# Hardware-Neuron.net
KiCad netlist of a schematic drawn in EAGLE
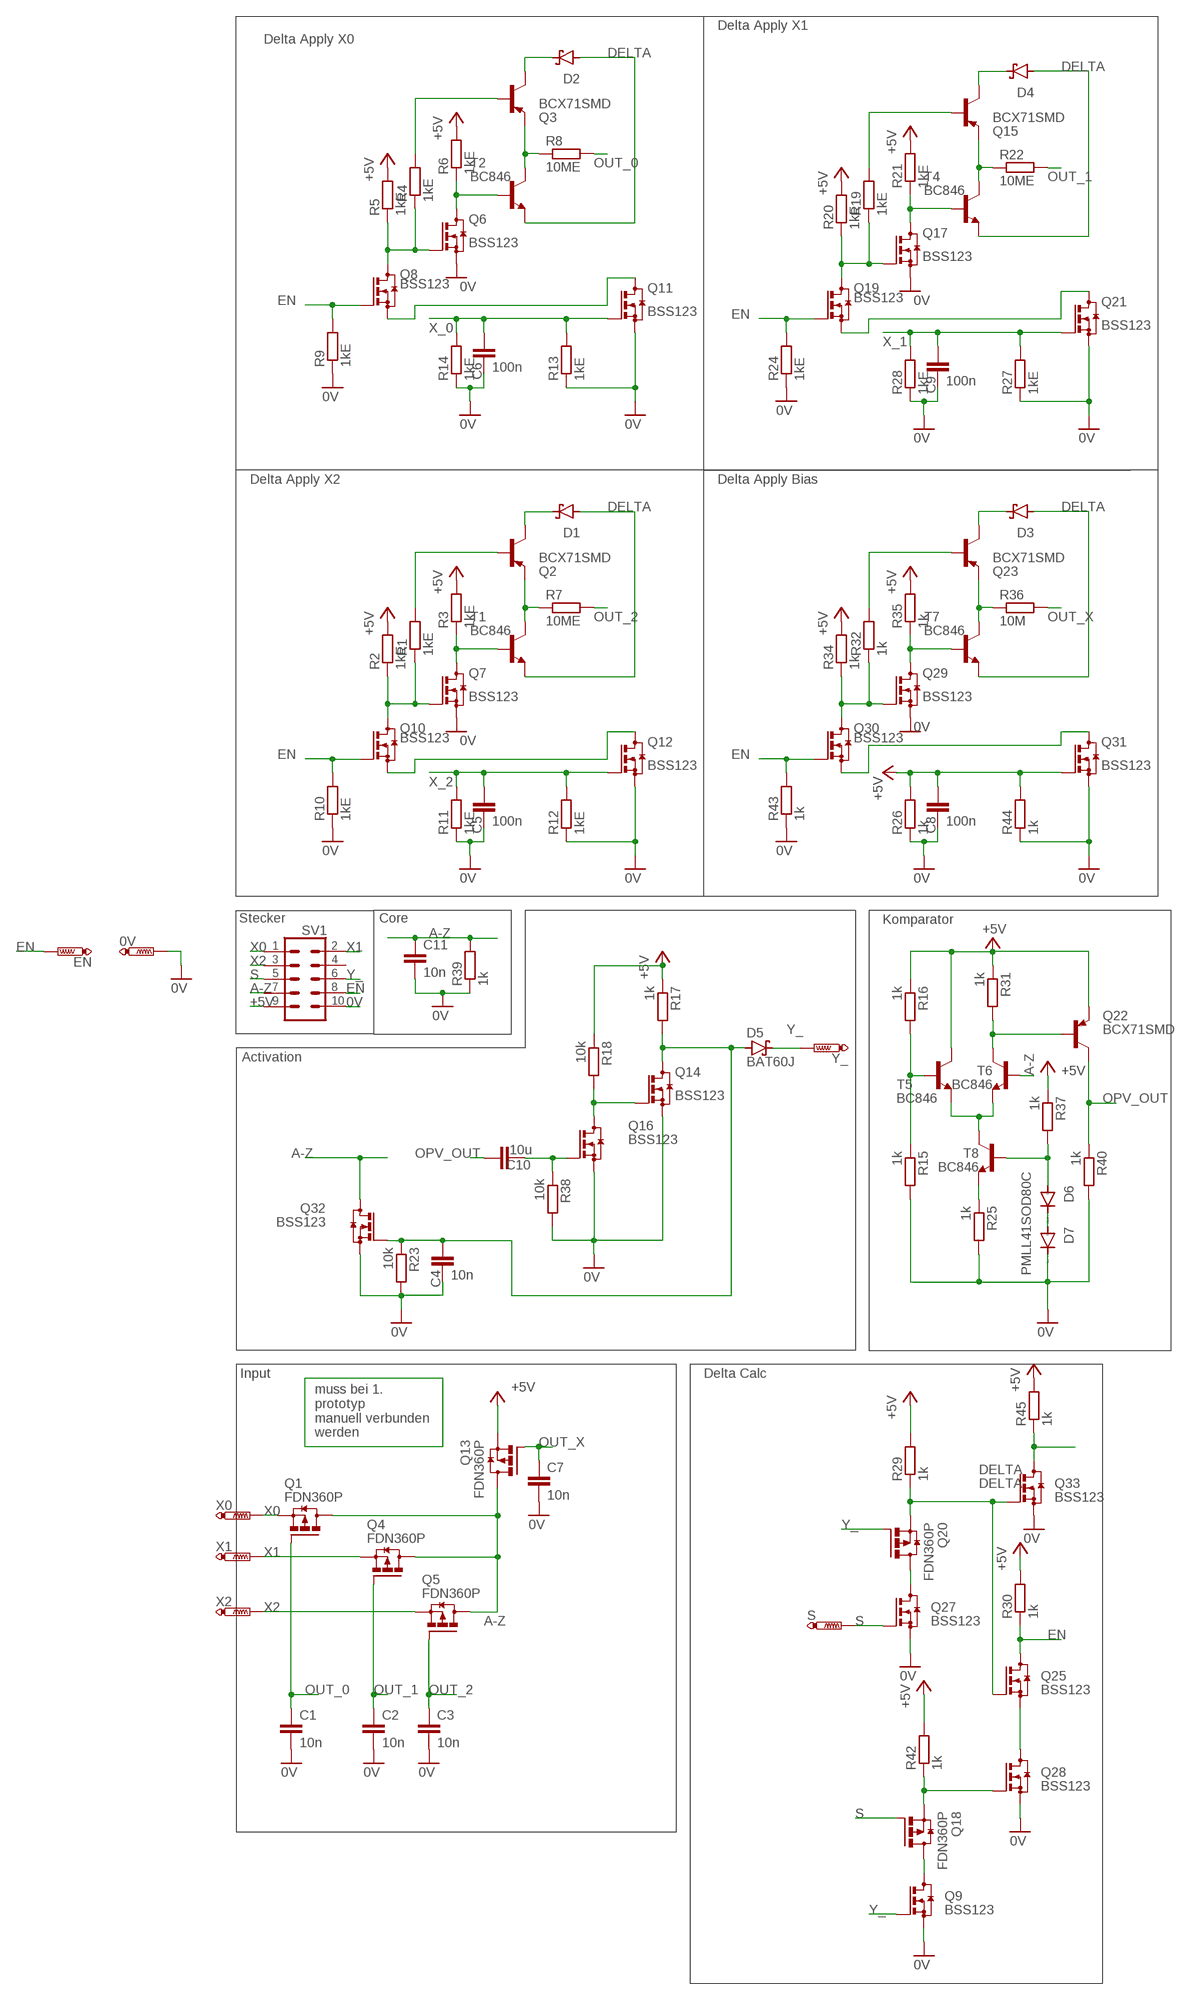
[diagram p0: schematic, sheet 1]

(export (version "E")
  (design (tool "Eeschema 10.0.6"))
  (components
    (comp (ref "0V")
      (value "PTR1PAD1-17")
      (footprint "eagle-import:P1-17")
      (libsource (lib "eagle-import") (part "PTR1PAD1-17"))
    )
    (comp (ref "C1")
      (value "10n")
      (footprint "eagle-import:C0805")
      (libsource (lib "eagle-import") (part "C-EUC0805"))
    )
    (comp (ref "C2")
      (value "10n")
      (footprint "eagle-import:C0805")
      (libsource (lib "eagle-import") (part "C-EUC0805"))
    )
    (comp (ref "C3")
      (value "10n")
      (footprint "eagle-import:C0805")
      (libsource (lib "eagle-import") (part "C-EUC0805"))
    )
    (comp (ref "C4")
      (value "10n")
      (footprint "eagle-import:C0805")
      (libsource (lib "eagle-import") (part "C-EUC0805"))
    )
    (comp (ref "C5")
      (value "100n")
      (footprint "eagle-import:C0805")
      (libsource (lib "eagle-import") (part "C-EUC0805"))
    )
    (comp (ref "C6")
      (value "100n")
      (footprint "eagle-import:C0805")
      (libsource (lib "eagle-import") (part "C-EUC0805"))
    )
    (comp (ref "C7")
      (value "10n")
      (footprint "eagle-import:C0805")
      (libsource (lib "eagle-import") (part "C-EUC0805"))
    )
    (comp (ref "C8")
      (value "100n")
      (footprint "eagle-import:C0805")
      (libsource (lib "eagle-import") (part "C-EUC0805"))
    )
    (comp (ref "C9")
      (value "100n")
      (footprint "eagle-import:C0805")
      (libsource (lib "eagle-import") (part "C-EUC0805"))
    )
    (comp (ref "C10")
      (value "10u")
      (footprint "eagle-import:C0805")
      (libsource (lib "eagle-import") (part "C-EUC0805"))
    )
    (comp (ref "C11")
      (value "10n")
      (footprint "eagle-import:C0805")
      (libsource (lib "eagle-import") (part "C-EUC0805"))
    )
    (comp (ref "D1")
      (value "BAT60J")
      (footprint "eagle-import:SOD323_ST")
      (libsource (lib "eagle-import") (part "BAT60J"))
    )
    (comp (ref "D2")
      (value "BAT60J")
      (footprint "eagle-import:SOD323_ST")
      (libsource (lib "eagle-import") (part "BAT60J"))
    )
    (comp (ref "D3")
      (value "BAT60J")
      (footprint "eagle-import:SOD323_ST")
      (libsource (lib "eagle-import") (part "BAT60J"))
    )
    (comp (ref "D4")
      (value "BAT60J")
      (footprint "eagle-import:SOD323_ST")
      (libsource (lib "eagle-import") (part "BAT60J"))
    )
    (comp (ref "D5")
      (value "BAT60J")
      (footprint "eagle-import:SOD323_ST")
      (libsource (lib "eagle-import") (part "BAT60J"))
    )
    (comp (ref "D6")
      (value "PMLL41SOD80C")
      (footprint "eagle-import:SOD80C")
      (libsource (lib "eagle-import") (part "PMLL41SOD80C"))
    )
    (comp (ref "D7")
      (value "PMLL41SOD80C")
      (footprint "eagle-import:SOD80C")
      (libsource (lib "eagle-import") (part "PMLL41SOD80C"))
    )
    (comp (ref "EN")
      (value "PTR1PAD1-17")
      (footprint "eagle-import:P1-17")
      (libsource (lib "eagle-import") (part "PTR1PAD1-17"))
    )
    (comp (ref "Q1")
      (value "FDN360P")
      (footprint "eagle-import:SUPER-SOT3")
      (libsource (lib "eagle-import") (part "FDN360P"))
    )
    (comp (ref "Q2")
      (value "BCX71SMD")
      (footprint "eagle-import:SOT23")
      (libsource (lib "eagle-import") (part "BCX71SMD"))
    )
    (comp (ref "Q3")
      (value "BCX71SMD")
      (footprint "eagle-import:SOT23")
      (libsource (lib "eagle-import") (part "BCX71SMD"))
    )
    (comp (ref "Q4")
      (value "FDN360P")
      (footprint "eagle-import:SUPER-SOT3")
      (libsource (lib "eagle-import") (part "FDN360P"))
    )
    (comp (ref "Q5")
      (value "FDN360P")
      (footprint "eagle-import:SUPER-SOT3")
      (libsource (lib "eagle-import") (part "FDN360P"))
    )
    (comp (ref "Q6")
      (value "BSS123")
      (footprint "eagle-import:SOT23")
      (libsource (lib "eagle-import") (part "BSS123"))
    )
    (comp (ref "Q7")
      (value "BSS123")
      (footprint "eagle-import:SOT23")
      (libsource (lib "eagle-import") (part "BSS123"))
    )
    (comp (ref "Q8")
      (value "BSS123")
      (footprint "eagle-import:SOT23")
      (libsource (lib "eagle-import") (part "BSS123"))
    )
    (comp (ref "Q9")
      (value "BSS123")
      (footprint "eagle-import:SOT23")
      (libsource (lib "eagle-import") (part "BSS123"))
    )
    (comp (ref "Q10")
      (value "BSS123")
      (footprint "eagle-import:SOT23")
      (libsource (lib "eagle-import") (part "BSS123"))
    )
    (comp (ref "Q11")
      (value "BSS123")
      (footprint "eagle-import:SOT23")
      (libsource (lib "eagle-import") (part "BSS123"))
    )
    (comp (ref "Q12")
      (value "BSS123")
      (footprint "eagle-import:SOT23")
      (libsource (lib "eagle-import") (part "BSS123"))
    )
    (comp (ref "Q13")
      (value "FDN360P")
      (footprint "eagle-import:SUPER-SOT3")
      (libsource (lib "eagle-import") (part "FDN360P"))
    )
    (comp (ref "Q14")
      (value "BSS123")
      (footprint "eagle-import:SOT23")
      (libsource (lib "eagle-import") (part "BSS123"))
    )
    (comp (ref "Q15")
      (value "BCX71SMD")
      (footprint "eagle-import:SOT23")
      (libsource (lib "eagle-import") (part "BCX71SMD"))
    )
    (comp (ref "Q16")
      (value "BSS123")
      (footprint "eagle-import:SOT23")
      (libsource (lib "eagle-import") (part "BSS123"))
    )
    (comp (ref "Q17")
      (value "BSS123")
      (footprint "eagle-import:SOT23")
      (libsource (lib "eagle-import") (part "BSS123"))
    )
    (comp (ref "Q18")
      (value "FDN360P")
      (footprint "eagle-import:SUPER-SOT3")
      (libsource (lib "eagle-import") (part "FDN360P"))
    )
    (comp (ref "Q19")
      (value "BSS123")
      (footprint "eagle-import:SOT23")
      (libsource (lib "eagle-import") (part "BSS123"))
    )
    (comp (ref "Q20")
      (value "FDN360P")
      (footprint "eagle-import:SUPER-SOT3")
      (libsource (lib "eagle-import") (part "FDN360P"))
    )
    (comp (ref "Q21")
      (value "BSS123")
      (footprint "eagle-import:SOT23")
      (libsource (lib "eagle-import") (part "BSS123"))
    )
    (comp (ref "Q22")
      (value "BCX71SMD")
      (footprint "eagle-import:SOT23")
      (libsource (lib "eagle-import") (part "BCX71SMD"))
    )
    (comp (ref "Q23")
      (value "BCX71SMD")
      (footprint "eagle-import:SOT23")
      (libsource (lib "eagle-import") (part "BCX71SMD"))
    )
    (comp (ref "Q25")
      (value "BSS123")
      (footprint "eagle-import:SOT23")
      (libsource (lib "eagle-import") (part "BSS123"))
    )
    (comp (ref "Q27")
      (value "BSS123")
      (footprint "eagle-import:SOT23")
      (libsource (lib "eagle-import") (part "BSS123"))
    )
    (comp (ref "Q28")
      (value "BSS123")
      (footprint "eagle-import:SOT23")
      (libsource (lib "eagle-import") (part "BSS123"))
    )
    (comp (ref "Q29")
      (value "BSS123")
      (footprint "eagle-import:SOT23")
      (libsource (lib "eagle-import") (part "BSS123"))
    )
    (comp (ref "Q30")
      (value "BSS123")
      (footprint "eagle-import:SOT23")
      (libsource (lib "eagle-import") (part "BSS123"))
    )
    (comp (ref "Q31")
      (value "BSS123")
      (footprint "eagle-import:SOT23")
      (libsource (lib "eagle-import") (part "BSS123"))
    )
    (comp (ref "Q32")
      (value "BSS123")
      (footprint "eagle-import:SOT23")
      (libsource (lib "eagle-import") (part "BSS123"))
    )
    (comp (ref "Q33")
      (value "BSS123")
      (footprint "eagle-import:SOT23")
      (libsource (lib "eagle-import") (part "BSS123"))
    )
    (comp (ref "R1")
      (value "1kE")
      (footprint "eagle-import:M0805")
      (libsource (lib "eagle-import") (part "R-EU_M0805"))
    )
    (comp (ref "R2")
      (value "1kE")
      (footprint "eagle-import:M0805")
      (libsource (lib "eagle-import") (part "R-EU_M0805"))
    )
    (comp (ref "R3")
      (value "1kE")
      (footprint "eagle-import:M0805")
      (libsource (lib "eagle-import") (part "R-EU_M0805"))
    )
    (comp (ref "R4")
      (value "1kE")
      (footprint "eagle-import:M0805")
      (libsource (lib "eagle-import") (part "R-EU_M0805"))
    )
    (comp (ref "R5")
      (value "1kE")
      (footprint "eagle-import:M0805")
      (libsource (lib "eagle-import") (part "R-EU_M0805"))
    )
    (comp (ref "R6")
      (value "1kE")
      (footprint "eagle-import:M0805")
      (libsource (lib "eagle-import") (part "R-EU_M0805"))
    )
    (comp (ref "R7")
      (value "10ME")
      (footprint "eagle-import:M0805")
      (libsource (lib "eagle-import") (part "R-EU_M0805"))
    )
    (comp (ref "R8")
      (value "10ME")
      (footprint "eagle-import:M0805")
      (libsource (lib "eagle-import") (part "R-EU_M0805"))
    )
    (comp (ref "R9")
      (value "1kE")
      (footprint "eagle-import:M0805")
      (libsource (lib "eagle-import") (part "R-EU_M0805"))
    )
    (comp (ref "R10")
      (value "1kE")
      (footprint "eagle-import:M0805")
      (libsource (lib "eagle-import") (part "R-EU_M0805"))
    )
    (comp (ref "R11")
      (value "1kE")
      (footprint "eagle-import:M0805")
      (libsource (lib "eagle-import") (part "R-EU_M0805"))
    )
    (comp (ref "R12")
      (value "1kE")
      (footprint "eagle-import:M0805")
      (libsource (lib "eagle-import") (part "R-EU_M0805"))
    )
    (comp (ref "R13")
      (value "1kE")
      (footprint "eagle-import:M0805")
      (libsource (lib "eagle-import") (part "R-EU_M0805"))
    )
    (comp (ref "R14")
      (value "1kE")
      (footprint "eagle-import:M0805")
      (libsource (lib "eagle-import") (part "R-EU_M0805"))
    )
    (comp (ref "R15")
      (value "1k")
      (footprint "eagle-import:M0805")
      (libsource (lib "eagle-import") (part "R-EU_M0805"))
    )
    (comp (ref "R16")
      (value "1k")
      (footprint "eagle-import:M0805")
      (libsource (lib "eagle-import") (part "R-EU_M0805"))
    )
    (comp (ref "R17")
      (value "1k")
      (footprint "eagle-import:M0805")
      (libsource (lib "eagle-import") (part "R-EU_M0805"))
    )
    (comp (ref "R18")
      (value "10k")
      (footprint "eagle-import:M0805")
      (libsource (lib "eagle-import") (part "R-EU_M0805"))
    )
    (comp (ref "R19")
      (value "1kE")
      (footprint "eagle-import:M0805")
      (libsource (lib "eagle-import") (part "R-EU_M0805"))
    )
    (comp (ref "R20")
      (value "1kE")
      (footprint "eagle-import:M0805")
      (libsource (lib "eagle-import") (part "R-EU_M0805"))
    )
    (comp (ref "R21")
      (value "1kE")
      (footprint "eagle-import:M0805")
      (libsource (lib "eagle-import") (part "R-EU_M0805"))
    )
    (comp (ref "R22")
      (value "10ME")
      (footprint "eagle-import:M0805")
      (libsource (lib "eagle-import") (part "R-EU_M0805"))
    )
    (comp (ref "R23")
      (value "10k")
      (footprint "eagle-import:M0805")
      (libsource (lib "eagle-import") (part "R-EU_M0805"))
    )
    (comp (ref "R24")
      (value "1kE")
      (footprint "eagle-import:M0805")
      (libsource (lib "eagle-import") (part "R-EU_M0805"))
    )
    (comp (ref "R25")
      (value "1k")
      (footprint "eagle-import:M0805")
      (libsource (lib "eagle-import") (part "R-EU_M0805"))
    )
    (comp (ref "R26")
      (value "1k")
      (footprint "eagle-import:M0805")
      (libsource (lib "eagle-import") (part "R-EU_M0805"))
    )
    (comp (ref "R27")
      (value "1kE")
      (footprint "eagle-import:M0805")
      (libsource (lib "eagle-import") (part "R-EU_M0805"))
    )
    (comp (ref "R28")
      (value "1kE")
      (footprint "eagle-import:M0805")
      (libsource (lib "eagle-import") (part "R-EU_M0805"))
    )
    (comp (ref "R29")
      (value "1k")
      (footprint "eagle-import:M0805")
      (libsource (lib "eagle-import") (part "R-EU_M0805"))
    )
    (comp (ref "R30")
      (value "1k")
      (footprint "eagle-import:M0805")
      (libsource (lib "eagle-import") (part "R-EU_M0805"))
    )
    (comp (ref "R31")
      (value "1k")
      (footprint "eagle-import:M0805")
      (libsource (lib "eagle-import") (part "R-EU_M0805"))
    )
    (comp (ref "R32")
      (value "1k")
      (footprint "eagle-import:M0805")
      (libsource (lib "eagle-import") (part "R-EU_M0805"))
    )
    (comp (ref "R34")
      (value "1k")
      (footprint "eagle-import:M0805")
      (libsource (lib "eagle-import") (part "R-EU_M0805"))
    )
    (comp (ref "R35")
      (value "1k")
      (footprint "eagle-import:M0805")
      (libsource (lib "eagle-import") (part "R-EU_M0805"))
    )
    (comp (ref "R36")
      (value "10M")
      (footprint "eagle-import:M0805")
      (libsource (lib "eagle-import") (part "R-EU_M0805"))
    )
    (comp (ref "R37")
      (value "1k")
      (footprint "eagle-import:M0805")
      (libsource (lib "eagle-import") (part "R-EU_M0805"))
    )
    (comp (ref "R38")
      (value "10k")
      (footprint "eagle-import:M0805")
      (libsource (lib "eagle-import") (part "R-EU_M0805"))
    )
    (comp (ref "R39")
      (value "1k")
      (footprint "eagle-import:M0805")
      (libsource (lib "eagle-import") (part "R-EU_M0805"))
    )
    (comp (ref "R40")
      (value "1k")
      (footprint "eagle-import:M0805")
      (libsource (lib "eagle-import") (part "R-EU_M0805"))
    )
    (comp (ref "R42")
      (value "1k")
      (footprint "eagle-import:M0805")
      (libsource (lib "eagle-import") (part "R-EU_M0805"))
    )
    (comp (ref "R43")
      (value "1k")
      (footprint "eagle-import:M0805")
      (libsource (lib "eagle-import") (part "R-EU_M0805"))
    )
    (comp (ref "R44")
      (value "1k")
      (footprint "eagle-import:M0805")
      (libsource (lib "eagle-import") (part "R-EU_M0805"))
    )
    (comp (ref "R45")
      (value "1k")
      (footprint "eagle-import:M0805")
      (libsource (lib "eagle-import") (part "R-EU_M0805"))
    )
    (comp (ref "S")
      (value "PTR1PAD1-17")
      (footprint "eagle-import:P1-17")
      (libsource (lib "eagle-import") (part "PTR1PAD1-17"))
    )
    (comp (ref "SV1")
      (value "ML10")
      (footprint "eagle-import:ML10")
      (libsource (lib "eagle-import") (part "ML10"))
    )
    (comp (ref "T1")
      (value "BC846")
      (footprint "eagle-import:SOT23")
      (libsource (lib "eagle-import") (part "BC846"))
    )
    (comp (ref "T2")
      (value "BC846")
      (footprint "eagle-import:SOT23")
      (libsource (lib "eagle-import") (part "BC846"))
    )
    (comp (ref "T4")
      (value "BC846")
      (footprint "eagle-import:SOT23")
      (libsource (lib "eagle-import") (part "BC846"))
    )
    (comp (ref "T5")
      (value "BC846")
      (footprint "eagle-import:SOT23")
      (libsource (lib "eagle-import") (part "BC846"))
    )
    (comp (ref "T6")
      (value "BC846")
      (footprint "eagle-import:SOT23")
      (libsource (lib "eagle-import") (part "BC846"))
    )
    (comp (ref "T7")
      (value "BC846")
      (footprint "eagle-import:SOT23")
      (libsource (lib "eagle-import") (part "BC846"))
    )
    (comp (ref "T8")
      (value "BC846")
      (footprint "eagle-import:SOT23")
      (libsource (lib "eagle-import") (part "BC846"))
    )
    (comp (ref "X0")
      (value "PTR1PAD1-17")
      (footprint "eagle-import:P1-17")
      (libsource (lib "eagle-import") (part "PTR1PAD1-17"))
    )
    (comp (ref "X1")
      (value "PTR1PAD1-17")
      (footprint "eagle-import:P1-17")
      (libsource (lib "eagle-import") (part "PTR1PAD1-17"))
    )
    (comp (ref "X2")
      (value "PTR1PAD1-17")
      (footprint "eagle-import:P1-17")
      (libsource (lib "eagle-import") (part "PTR1PAD1-17"))
    )
    (comp (ref "Y_")
      (value "PTR1PAD1-17")
      (footprint "eagle-import:P1-17")
      (libsource (lib "eagle-import") (part "PTR1PAD1-17"))
    )
  )
  (nets
    (net (code "1") (name "+5V") (class "Default")
      (node (ref "C8") (pin "1") (pinfunction "1_1") (pintype "passive"))
      (node (ref "Q13") (pin "2") (pinfunction "S_2") (pintype "passive"))
      (node (ref "Q22") (pin "2") (pinfunction "E_2") (pintype "passive"))
      (node (ref "Q31") (pin "1") (pinfunction "G_1") (pintype "passive"))
      (node (ref "R16") (pin "1") (pinfunction "1_1") (pintype "passive"))
      (node (ref "R17") (pin "1") (pinfunction "1_1") (pintype "passive"))
      (node (ref "R18") (pin "1") (pinfunction "1_1") (pintype "passive"))
      (node (ref "R2") (pin "2") (pinfunction "2_2") (pintype "passive"))
      (node (ref "R20") (pin "2") (pinfunction "2_2") (pintype "passive"))
      (node (ref "R21") (pin "2") (pinfunction "2_2") (pintype "passive"))
      (node (ref "R26") (pin "2") (pinfunction "2_2") (pintype "passive"))
      (node (ref "R29") (pin "2") (pinfunction "2_2") (pintype "passive"))
      (node (ref "R3") (pin "2") (pinfunction "2_2") (pintype "passive"))
      (node (ref "R30") (pin "2") (pinfunction "2_2") (pintype "passive"))
      (node (ref "R31") (pin "1") (pinfunction "1_1") (pintype "passive"))
      (node (ref "R34") (pin "2") (pinfunction "2_2") (pintype "passive"))
      (node (ref "R35") (pin "2") (pinfunction "2_2") (pintype "passive"))
      (node (ref "R37") (pin "1") (pinfunction "1_1") (pintype "passive"))
      (node (ref "R42") (pin "2") (pinfunction "2_2") (pintype "passive"))
      (node (ref "R44") (pin "2") (pinfunction "2_2") (pintype "passive"))
      (node (ref "R45") (pin "2") (pinfunction "2_2") (pintype "passive"))
      (node (ref "R5") (pin "2") (pinfunction "2_2") (pintype "passive"))
      (node (ref "R6") (pin "2") (pinfunction "2_2") (pintype "passive"))
      (node (ref "SV1") (pin "9") (pinfunction "9_9") (pintype "passive"))
      (node (ref "T5") (pin "3") (pinfunction "C_3") (pintype "passive"))
    )
    (net (code "2") (name "/A-Z") (class "Default")
      (node (ref "C11") (pin "1") (pinfunction "1_1") (pintype "passive"))
      (node (ref "Q1") (pin "3") (pinfunction "D_3") (pintype "passive"))
      (node (ref "Q13") (pin "3") (pinfunction "D_3") (pintype "passive"))
      (node (ref "Q32") (pin "3") (pinfunction "D_3") (pintype "passive"))
      (node (ref "Q4") (pin "3") (pinfunction "D_3") (pintype "passive"))
      (node (ref "Q5") (pin "3") (pinfunction "D_3") (pintype "passive"))
      (node (ref "R39") (pin "2") (pinfunction "2_2") (pintype "passive"))
      (node (ref "SV1") (pin "7") (pinfunction "7_7") (pintype "passive"))
      (node (ref "T6") (pin "1") (pinfunction "B_1") (pintype "passive"))
    )
    (net (code "3") (name "/DELTA") (class "Default")
      (node (ref "D1") (pin "A") (pinfunction "A_A") (pintype "passive"))
      (node (ref "D2") (pin "A") (pinfunction "A_A") (pintype "passive"))
      (node (ref "D3") (pin "A") (pinfunction "A_A") (pintype "passive"))
      (node (ref "D4") (pin "A") (pinfunction "A_A") (pintype "passive"))
      (node (ref "Q20") (pin "2") (pinfunction "S_2") (pintype "passive"))
      (node (ref "Q25") (pin "1") (pinfunction "G_1") (pintype "passive"))
      (node (ref "Q33") (pin "1") (pinfunction "G_1") (pintype "passive"))
      (node (ref "R29") (pin "1") (pinfunction "1_1") (pintype "passive"))
      (node (ref "T1") (pin "2") (pinfunction "E_2") (pintype "passive"))
      (node (ref "T2") (pin "2") (pinfunction "E_2") (pintype "passive"))
      (node (ref "T4") (pin "2") (pinfunction "E_2") (pintype "passive"))
      (node (ref "T7") (pin "2") (pinfunction "E_2") (pintype "passive"))
    )
    (net (code "4") (name "/EN") (class "Default")
      (node (ref "EN") (pin "TP") (pinfunction "TP_TP") (pintype "input"))
      (node (ref "Q10") (pin "1") (pinfunction "G_1") (pintype "passive"))
      (node (ref "Q19") (pin "1") (pinfunction "G_1") (pintype "passive"))
      (node (ref "Q25") (pin "3") (pinfunction "D_3") (pintype "passive"))
      (node (ref "Q30") (pin "1") (pinfunction "G_1") (pintype "passive"))
      (node (ref "Q8") (pin "1") (pinfunction "G_1") (pintype "passive"))
      (node (ref "R10") (pin "2") (pinfunction "2_2") (pintype "passive"))
      (node (ref "R24") (pin "2") (pinfunction "2_2") (pintype "passive"))
      (node (ref "R30") (pin "1") (pinfunction "1_1") (pintype "passive"))
      (node (ref "R43") (pin "2") (pinfunction "2_2") (pintype "passive"))
      (node (ref "R9") (pin "2") (pinfunction "2_2") (pintype "passive"))
      (node (ref "SV1") (pin "8") (pinfunction "8_8") (pintype "passive"))
    )
    (net (code "5") (name "/OPV_OUT") (class "Default")
      (node (ref "C10") (pin "1") (pinfunction "1_1") (pintype "passive"))
      (node (ref "Q22") (pin "3") (pinfunction "C_3") (pintype "passive"))
      (node (ref "R40") (pin "1") (pinfunction "1_1") (pintype "passive"))
    )
    (net (code "6") (name "/OUT_0") (class "Default")
      (node (ref "C1") (pin "1") (pinfunction "1_1") (pintype "passive"))
      (node (ref "Q1") (pin "1") (pinfunction "G_1") (pintype "passive"))
      (node (ref "R8") (pin "2") (pinfunction "2_2") (pintype "passive"))
    )
    (net (code "7") (name "/OUT_1") (class "Default")
      (node (ref "C2") (pin "1") (pinfunction "1_1") (pintype "passive"))
      (node (ref "Q4") (pin "1") (pinfunction "G_1") (pintype "passive"))
      (node (ref "R22") (pin "2") (pinfunction "2_2") (pintype "passive"))
    )
    (net (code "8") (name "/OUT_2") (class "Default")
      (node (ref "C3") (pin "1") (pinfunction "1_1") (pintype "passive"))
      (node (ref "Q5") (pin "1") (pinfunction "G_1") (pintype "passive"))
      (node (ref "R7") (pin "2") (pinfunction "2_2") (pintype "passive"))
    )
    (net (code "9") (name "/OUT_X") (class "Default")
      (node (ref "C7") (pin "1") (pinfunction "1_1") (pintype "passive"))
      (node (ref "Q13") (pin "1") (pinfunction "G_1") (pintype "passive"))
      (node (ref "R36") (pin "2") (pinfunction "2_2") (pintype "passive"))
    )
    (net (code "10") (name "/S") (class "Default")
      (node (ref "Q18") (pin "1") (pinfunction "G_1") (pintype "passive"))
      (node (ref "Q27") (pin "1") (pinfunction "G_1") (pintype "passive"))
      (node (ref "S") (pin "TP") (pinfunction "TP_TP") (pintype "input"))
      (node (ref "SV1") (pin "5") (pinfunction "5_5") (pintype "passive"))
    )
    (net (code "11") (name "/X0") (class "Default")
      (node (ref "Q1") (pin "2") (pinfunction "S_2") (pintype "passive"))
      (node (ref "SV1") (pin "1") (pinfunction "1_1") (pintype "passive"))
      (node (ref "X0") (pin "TP") (pinfunction "TP_TP") (pintype "input"))
    )
    (net (code "12") (name "/X1") (class "Default")
      (node (ref "Q4") (pin "2") (pinfunction "S_2") (pintype "passive"))
      (node (ref "SV1") (pin "2") (pinfunction "2_2") (pintype "passive"))
      (node (ref "X1") (pin "TP") (pinfunction "TP_TP") (pintype "input"))
    )
    (net (code "13") (name "/X2") (class "Default")
      (node (ref "Q5") (pin "2") (pinfunction "S_2") (pintype "passive"))
      (node (ref "SV1") (pin "3") (pinfunction "3_3") (pintype "passive"))
      (node (ref "X2") (pin "TP") (pinfunction "TP_TP") (pintype "input"))
    )
    (net (code "14") (name "/X_0") (class "Default")
      (node (ref "C6") (pin "1") (pinfunction "1_1") (pintype "passive"))
      (node (ref "Q11") (pin "1") (pinfunction "G_1") (pintype "passive"))
      (node (ref "R13") (pin "2") (pinfunction "2_2") (pintype "passive"))
      (node (ref "R14") (pin "2") (pinfunction "2_2") (pintype "passive"))
    )
    (net (code "15") (name "/X_1") (class "Default")
      (node (ref "C9") (pin "1") (pinfunction "1_1") (pintype "passive"))
      (node (ref "Q21") (pin "1") (pinfunction "G_1") (pintype "passive"))
      (node (ref "R27") (pin "2") (pinfunction "2_2") (pintype "passive"))
      (node (ref "R28") (pin "2") (pinfunction "2_2") (pintype "passive"))
    )
    (net (code "16") (name "/X_2") (class "Default")
      (node (ref "C5") (pin "1") (pinfunction "1_1") (pintype "passive"))
      (node (ref "Q12") (pin "1") (pinfunction "G_1") (pintype "passive"))
      (node (ref "R11") (pin "2") (pinfunction "2_2") (pintype "passive"))
      (node (ref "R12") (pin "2") (pinfunction "2_2") (pintype "passive"))
    )
    (net (code "17") (name "/Y_") (class "Default")
      (node (ref "D5") (pin "C") (pinfunction "C_C") (pintype "passive"))
      (node (ref "Q20") (pin "1") (pinfunction "G_1") (pintype "passive"))
      (node (ref "Q9") (pin "1") (pinfunction "G_1") (pintype "passive"))
      (node (ref "SV1") (pin "6") (pinfunction "6_6") (pintype "passive"))
      (node (ref "Y_") (pin "TP") (pinfunction "TP_TP") (pintype "input"))
    )
    (net (code "18") (name "0V") (class "Default")
      (node (ref "0V") (pin "TP") (pinfunction "TP_TP") (pintype "input"))
      (node (ref "C1") (pin "2") (pinfunction "2_2") (pintype "passive"))
      (node (ref "C11") (pin "2") (pinfunction "2_2") (pintype "passive"))
      (node (ref "C2") (pin "2") (pinfunction "2_2") (pintype "passive"))
      (node (ref "C3") (pin "2") (pinfunction "2_2") (pintype "passive"))
      (node (ref "C4") (pin "2") (pinfunction "2_2") (pintype "passive"))
      (node (ref "C5") (pin "2") (pinfunction "2_2") (pintype "passive"))
      (node (ref "C6") (pin "2") (pinfunction "2_2") (pintype "passive"))
      (node (ref "C7") (pin "2") (pinfunction "2_2") (pintype "passive"))
      (node (ref "C8") (pin "2") (pinfunction "2_2") (pintype "passive"))
      (node (ref "C9") (pin "2") (pinfunction "2_2") (pintype "passive"))
      (node (ref "D7") (pin "C") (pinfunction "C_C") (pintype "passive"))
      (node (ref "Q11") (pin "2") (pinfunction "S_2") (pintype "passive"))
      (node (ref "Q12") (pin "2") (pinfunction "S_2") (pintype "passive"))
      (node (ref "Q14") (pin "2") (pinfunction "S_2") (pintype "passive"))
      (node (ref "Q16") (pin "2") (pinfunction "S_2") (pintype "passive"))
      (node (ref "Q17") (pin "2") (pinfunction "S_2") (pintype "passive"))
      (node (ref "Q21") (pin "2") (pinfunction "S_2") (pintype "passive"))
      (node (ref "Q27") (pin "2") (pinfunction "S_2") (pintype "passive"))
      (node (ref "Q28") (pin "2") (pinfunction "S_2") (pintype "passive"))
      (node (ref "Q29") (pin "2") (pinfunction "S_2") (pintype "passive"))
      (node (ref "Q31") (pin "2") (pinfunction "S_2") (pintype "passive"))
      (node (ref "Q32") (pin "2") (pinfunction "S_2") (pintype "passive"))
      (node (ref "Q33") (pin "2") (pinfunction "S_2") (pintype "passive"))
      (node (ref "Q6") (pin "2") (pinfunction "S_2") (pintype "passive"))
      (node (ref "Q7") (pin "2") (pinfunction "S_2") (pintype "passive"))
      (node (ref "Q9") (pin "2") (pinfunction "S_2") (pintype "passive"))
      (node (ref "R10") (pin "1") (pinfunction "1_1") (pintype "passive"))
      (node (ref "R11") (pin "1") (pinfunction "1_1") (pintype "passive"))
      (node (ref "R12") (pin "1") (pinfunction "1_1") (pintype "passive"))
      (node (ref "R13") (pin "1") (pinfunction "1_1") (pintype "passive"))
      (node (ref "R14") (pin "1") (pinfunction "1_1") (pintype "passive"))
      (node (ref "R15") (pin "2") (pinfunction "2_2") (pintype "passive"))
      (node (ref "R23") (pin "2") (pinfunction "2_2") (pintype "passive"))
      (node (ref "R24") (pin "1") (pinfunction "1_1") (pintype "passive"))
      (node (ref "R25") (pin "2") (pinfunction "2_2") (pintype "passive"))
      (node (ref "R26") (pin "1") (pinfunction "1_1") (pintype "passive"))
      (node (ref "R27") (pin "1") (pinfunction "1_1") (pintype "passive"))
      (node (ref "R28") (pin "1") (pinfunction "1_1") (pintype "passive"))
      (node (ref "R38") (pin "2") (pinfunction "2_2") (pintype "passive"))
      (node (ref "R39") (pin "1") (pinfunction "1_1") (pintype "passive"))
      (node (ref "R40") (pin "2") (pinfunction "2_2") (pintype "passive"))
      (node (ref "R43") (pin "1") (pinfunction "1_1") (pintype "passive"))
      (node (ref "R44") (pin "1") (pinfunction "1_1") (pintype "passive"))
      (node (ref "R9") (pin "1") (pinfunction "1_1") (pintype "passive"))
      (node (ref "SV1") (pin "10") (pinfunction "10_10") (pintype "passive"))
    )
    (net (code "19") (name "Net-(D6-PadC)") (class "Default")
      (node (ref "D6") (pin "C") (pinfunction "C_C") (pintype "passive"))
      (node (ref "D7") (pin "A") (pinfunction "A_A") (pintype "passive"))
    )
    (net (code "20") (name "Net-(Q2-B)") (class "Default")
      (node (ref "Q2") (pin "1") (pinfunction "B_1") (pintype "passive"))
      (node (ref "R1") (pin "2") (pinfunction "2_2") (pintype "passive"))
    )
    (net (code "21") (name "Net-(Q2-C)") (class "Default")
      (node (ref "D1") (pin "C") (pinfunction "C_C") (pintype "passive"))
      (node (ref "Q2") (pin "3") (pinfunction "C_3") (pintype "passive"))
    )
    (net (code "22") (name "Net-(Q2-E)") (class "Default")
      (node (ref "Q2") (pin "2") (pinfunction "E_2") (pintype "passive"))
      (node (ref "R7") (pin "1") (pinfunction "1_1") (pintype "passive"))
      (node (ref "T1") (pin "3") (pinfunction "C_3") (pintype "passive"))
    )
    (net (code "23") (name "Net-(Q3-B)") (class "Default")
      (node (ref "Q3") (pin "1") (pinfunction "B_1") (pintype "passive"))
      (node (ref "R4") (pin "2") (pinfunction "2_2") (pintype "passive"))
    )
    (net (code "24") (name "Net-(Q3-C)") (class "Default")
      (node (ref "D2") (pin "C") (pinfunction "C_C") (pintype "passive"))
      (node (ref "Q3") (pin "3") (pinfunction "C_3") (pintype "passive"))
    )
    (net (code "25") (name "Net-(Q3-E)") (class "Default")
      (node (ref "Q3") (pin "2") (pinfunction "E_2") (pintype "passive"))
      (node (ref "R8") (pin "1") (pinfunction "1_1") (pintype "passive"))
      (node (ref "T2") (pin "3") (pinfunction "C_3") (pintype "passive"))
    )
    (net (code "26") (name "Net-(Q6-D)") (class "Default")
      (node (ref "Q6") (pin "3") (pinfunction "D_3") (pintype "passive"))
      (node (ref "R6") (pin "1") (pinfunction "1_1") (pintype "passive"))
      (node (ref "T2") (pin "1") (pinfunction "B_1") (pintype "passive"))
    )
    (net (code "27") (name "Net-(Q6-G)") (class "Default")
      (node (ref "Q6") (pin "1") (pinfunction "G_1") (pintype "passive"))
      (node (ref "Q8") (pin "3") (pinfunction "D_3") (pintype "passive"))
      (node (ref "R4") (pin "1") (pinfunction "1_1") (pintype "passive"))
      (node (ref "R5") (pin "1") (pinfunction "1_1") (pintype "passive"))
    )
    (net (code "28") (name "Net-(Q7-D)") (class "Default")
      (node (ref "Q7") (pin "3") (pinfunction "D_3") (pintype "passive"))
      (node (ref "R3") (pin "1") (pinfunction "1_1") (pintype "passive"))
      (node (ref "T1") (pin "1") (pinfunction "B_1") (pintype "passive"))
    )
    (net (code "29") (name "Net-(Q10-D)") (class "Default")
      (node (ref "Q10") (pin "3") (pinfunction "D_3") (pintype "passive"))
      (node (ref "Q7") (pin "1") (pinfunction "G_1") (pintype "passive"))
      (node (ref "R1") (pin "1") (pinfunction "1_1") (pintype "passive"))
      (node (ref "R2") (pin "1") (pinfunction "1_1") (pintype "passive"))
    )
    (net (code "30") (name "Net-(Q10-S)") (class "Default")
      (node (ref "Q10") (pin "2") (pinfunction "S_2") (pintype "passive"))
      (node (ref "Q12") (pin "3") (pinfunction "D_3") (pintype "passive"))
    )
    (net (code "31") (name "Net-(Q11-D)") (class "Default")
      (node (ref "Q11") (pin "3") (pinfunction "D_3") (pintype "passive"))
      (node (ref "Q8") (pin "2") (pinfunction "S_2") (pintype "passive"))
    )
    (net (code "32") (name "Net-(Q14-D)") (class "Default")
      (node (ref "C4") (pin "1") (pinfunction "1_1") (pintype "passive"))
      (node (ref "D5") (pin "A") (pinfunction "A_A") (pintype "passive"))
      (node (ref "Q14") (pin "3") (pinfunction "D_3") (pintype "passive"))
      (node (ref "Q32") (pin "1") (pinfunction "G_1") (pintype "passive"))
      (node (ref "R17") (pin "2") (pinfunction "2_2") (pintype "passive"))
      (node (ref "R23") (pin "1") (pinfunction "1_1") (pintype "passive"))
    )
    (net (code "33") (name "Net-(Q14-G)") (class "Default")
      (node (ref "Q14") (pin "1") (pinfunction "G_1") (pintype "passive"))
      (node (ref "Q16") (pin "3") (pinfunction "D_3") (pintype "passive"))
      (node (ref "R18") (pin "2") (pinfunction "2_2") (pintype "passive"))
    )
    (net (code "34") (name "Net-(Q15-B)") (class "Default")
      (node (ref "Q15") (pin "1") (pinfunction "B_1") (pintype "passive"))
      (node (ref "R19") (pin "2") (pinfunction "2_2") (pintype "passive"))
    )
    (net (code "35") (name "Net-(Q15-C)") (class "Default")
      (node (ref "D4") (pin "C") (pinfunction "C_C") (pintype "passive"))
      (node (ref "Q15") (pin "3") (pinfunction "C_3") (pintype "passive"))
    )
    (net (code "36") (name "Net-(Q15-E)") (class "Default")
      (node (ref "Q15") (pin "2") (pinfunction "E_2") (pintype "passive"))
      (node (ref "R22") (pin "1") (pinfunction "1_1") (pintype "passive"))
      (node (ref "T4") (pin "3") (pinfunction "C_3") (pintype "passive"))
    )
    (net (code "37") (name "Net-(Q16-G)") (class "Default")
      (node (ref "C10") (pin "2") (pinfunction "2_2") (pintype "passive"))
      (node (ref "Q16") (pin "1") (pinfunction "G_1") (pintype "passive"))
      (node (ref "R38") (pin "1") (pinfunction "1_1") (pintype "passive"))
    )
    (net (code "38") (name "Net-(Q17-D)") (class "Default")
      (node (ref "Q17") (pin "3") (pinfunction "D_3") (pintype "passive"))
      (node (ref "R21") (pin "1") (pinfunction "1_1") (pintype "passive"))
      (node (ref "T4") (pin "1") (pinfunction "B_1") (pintype "passive"))
    )
    (net (code "39") (name "Net-(Q17-G)") (class "Default")
      (node (ref "Q17") (pin "1") (pinfunction "G_1") (pintype "passive"))
      (node (ref "Q19") (pin "3") (pinfunction "D_3") (pintype "passive"))
      (node (ref "R19") (pin "1") (pinfunction "1_1") (pintype "passive"))
      (node (ref "R20") (pin "1") (pinfunction "1_1") (pintype "passive"))
    )
    (net (code "40") (name "Net-(Q18-D)") (class "Default")
      (node (ref "Q18") (pin "3") (pinfunction "D_3") (pintype "passive"))
      (node (ref "Q9") (pin "3") (pinfunction "D_3") (pintype "passive"))
    )
    (net (code "41") (name "Net-(Q18-S)") (class "Default")
      (node (ref "Q18") (pin "2") (pinfunction "S_2") (pintype "passive"))
      (node (ref "Q28") (pin "1") (pinfunction "G_1") (pintype "passive"))
      (node (ref "R42") (pin "1") (pinfunction "1_1") (pintype "passive"))
    )
    (net (code "42") (name "Net-(Q19-S)") (class "Default")
      (node (ref "Q19") (pin "2") (pinfunction "S_2") (pintype "passive"))
      (node (ref "Q21") (pin "3") (pinfunction "D_3") (pintype "passive"))
    )
    (net (code "43") (name "Net-(Q20-D)") (class "Default")
      (node (ref "Q20") (pin "3") (pinfunction "D_3") (pintype "passive"))
      (node (ref "Q27") (pin "3") (pinfunction "D_3") (pintype "passive"))
    )
    (net (code "44") (name "Net-(Q22-B)") (class "Default")
      (node (ref "Q22") (pin "1") (pinfunction "B_1") (pintype "passive"))
      (node (ref "R31") (pin "2") (pinfunction "2_2") (pintype "passive"))
      (node (ref "T6") (pin "3") (pinfunction "C_3") (pintype "passive"))
    )
    (net (code "45") (name "Net-(Q23-B)") (class "Default")
      (node (ref "Q23") (pin "1") (pinfunction "B_1") (pintype "passive"))
      (node (ref "R32") (pin "2") (pinfunction "2_2") (pintype "passive"))
    )
    (net (code "46") (name "Net-(Q23-C)") (class "Default")
      (node (ref "D3") (pin "C") (pinfunction "C_C") (pintype "passive"))
      (node (ref "Q23") (pin "3") (pinfunction "C_3") (pintype "passive"))
    )
    (net (code "47") (name "Net-(Q23-E)") (class "Default")
      (node (ref "Q23") (pin "2") (pinfunction "E_2") (pintype "passive"))
      (node (ref "R36") (pin "1") (pinfunction "1_1") (pintype "passive"))
      (node (ref "T7") (pin "3") (pinfunction "C_3") (pintype "passive"))
    )
    (net (code "48") (name "Net-(Q25-S)") (class "Default")
      (node (ref "Q25") (pin "2") (pinfunction "S_2") (pintype "passive"))
      (node (ref "Q28") (pin "3") (pinfunction "D_3") (pintype "passive"))
    )
    (net (code "49") (name "Net-(Q29-D)") (class "Default")
      (node (ref "Q29") (pin "3") (pinfunction "D_3") (pintype "passive"))
      (node (ref "R35") (pin "1") (pinfunction "1_1") (pintype "passive"))
      (node (ref "T7") (pin "1") (pinfunction "B_1") (pintype "passive"))
    )
    (net (code "50") (name "Net-(Q29-G)") (class "Default")
      (node (ref "Q29") (pin "1") (pinfunction "G_1") (pintype "passive"))
      (node (ref "Q30") (pin "3") (pinfunction "D_3") (pintype "passive"))
      (node (ref "R32") (pin "1") (pinfunction "1_1") (pintype "passive"))
      (node (ref "R34") (pin "1") (pinfunction "1_1") (pintype "passive"))
    )
    (net (code "51") (name "Net-(Q30-S)") (class "Default")
      (node (ref "Q30") (pin "2") (pinfunction "S_2") (pintype "passive"))
      (node (ref "Q31") (pin "3") (pinfunction "D_3") (pintype "passive"))
    )
    (net (code "52") (name "Net-(Q33-D)") (class "Default")
      (node (ref "Q33") (pin "3") (pinfunction "D_3") (pintype "passive"))
      (node (ref "R45") (pin "1") (pinfunction "1_1") (pintype "passive"))
    )
    (net (code "53") (name "Net-(T5-B)") (class "Default")
      (node (ref "R15") (pin "1") (pinfunction "1_1") (pintype "passive"))
      (node (ref "R16") (pin "2") (pinfunction "2_2") (pintype "passive"))
      (node (ref "T5") (pin "1") (pinfunction "B_1") (pintype "passive"))
    )
    (net (code "54") (name "Net-(T5-E)") (class "Default")
      (node (ref "T5") (pin "2") (pinfunction "E_2") (pintype "passive"))
      (node (ref "T6") (pin "2") (pinfunction "E_2") (pintype "passive"))
      (node (ref "T8") (pin "3") (pinfunction "C_3") (pintype "passive"))
    )
    (net (code "55") (name "Net-(T8-B)") (class "Default")
      (node (ref "D6") (pin "A") (pinfunction "A_A") (pintype "passive"))
      (node (ref "R37") (pin "2") (pinfunction "2_2") (pintype "passive"))
      (node (ref "T8") (pin "1") (pinfunction "B_1") (pintype "passive"))
    )
    (net (code "56") (name "Net-(T8-E)") (class "Default")
      (node (ref "R25") (pin "1") (pinfunction "1_1") (pintype "passive"))
      (node (ref "T8") (pin "2") (pinfunction "E_2") (pintype "passive"))
    )
    (net (code "57") (name "unconnected-(SV1-Pad4)") (class "Default")
      (node (ref "SV1") (pin "4") (pinfunction "4_4") (pintype "passive"))
    )
  )
)
